# 5V_regulators.net
KiCad netlist of a schematic drawn in Altium Designer
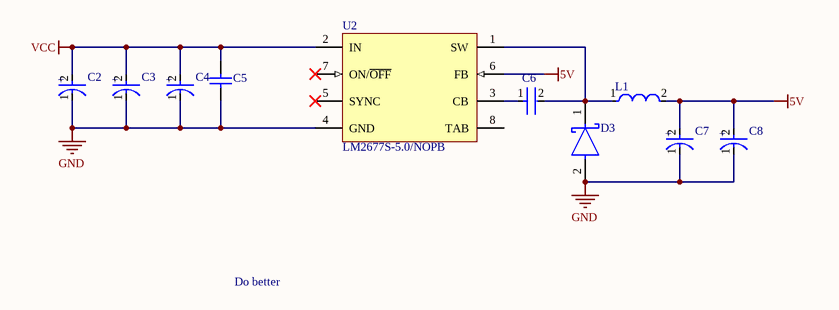
[diagram p0: 5V_regulators.SchDoc]

(export (version "E")
  (design (tool "Eeschema 10.0.6"))
  (components
    (comp (ref "C2")
      (value "16TQC15M")
      (footprint "FP-POSCAP-B2-MFG")
      (description "Molded Tantalum Polymer Capacitor 15uF 20% 16V life 2000Hours SMD 1411")
      (fields (field (name "VOLTAGE") "16V") (field (name "TOLERANCE") "20%"))
      (libsource (lib "Altium Content Vault") (part "cf48714ba7e38822c1575c7ec0b6d1f"))
    )
    (comp (ref "C3")
      (value "16TQC15M")
      (footprint "FP-POSCAP-B2-MFG")
      (description "Molded Tantalum Polymer Capacitor 15uF 20% 16V life 2000Hours SMD 1411")
      (fields (field (name "VOLTAGE") "16V") (field (name "TOLERANCE") "20%"))
      (libsource (lib "Altium Content Vault") (part "cf48714ba7e38822c1575c7ec0b6d1f"))
    )
    (comp (ref "C4")
      (value "16TQC15M")
      (footprint "FP-POSCAP-B2-MFG")
      (description "Molded Tantalum Polymer Capacitor 15uF 20% 16V life 2000Hours SMD 1411")
      (fields (field (name "VOLTAGE") "16V") (field (name "TOLERANCE") "20%"))
      (libsource (lib "Altium Content Vault") (part "cf48714ba7e38822c1575c7ec0b6d1f"))
    )
    (comp (ref "C5")
      (value "CAP 470nF 50V 1812(4532)")
      (footprint "CAPC1812(4532)125_M")
      (description "CAP 470nF 50V ±10% 1812 (4532 Metric) Thickness 1.25mm SMD")
      (fields (field (name "TOLERANCE") "Â±10%"))
      (libsource (lib "Altium Content Vault") (part "CAP"))
    )
    (comp (ref "C6")
      (value "C0805C103J5RACTU")
      (footprint "FP-C0805C-DN-MFG")
      (description "CAP CER 10000PF 50V X7R 0805")
      (fields
        (field (name "MANUFACTURER") "KEMET")
        (field (name "OCTOPART") "https://octopart.com/c0805c103j5ractu-kemet-133473")
      )
      (libsource (lib "Altium Content Vault") (part "b4654b650e69147ec39a6b967a45e02"))
    )
    (comp (ref "C7")
      (value "25SVPF180M")
      (footprint "FP-OS-CON-SMT-E12-MFG")
      (description "Conductive Polymer Aluminum Solid Capacitors (OS-CON) 180uF ±20% 25V")
      (fields (field (name "VOLTAGE") "25V") (field (name "TOLERANCE") "20%"))
      (libsource (lib "Altium Content Vault") (part "a00bbbee19879c290e62620ae7e47b1"))
    )
    (comp (ref "C8")
      (value "25SVPF180M")
      (footprint "FP-OS-CON-SMT-E12-MFG")
      (description "Conductive Polymer Aluminum Solid Capacitors (OS-CON) 180uF ±20% 25V")
      (fields (field (name "VOLTAGE") "25V") (field (name "TOLERANCE") "20%"))
      (libsource (lib "Altium Content Vault") (part "a00bbbee19879c290e62620ae7e47b1"))
    )
    (comp (ref "D3")
      (value "B540C-13-F")
      (footprint "FP-SMC-MFG")
      (description "DIODE SCHOTTKY 40V 5A SMC")
      (fields
        (field (name "OCTOPART") "https://octopart.com/b540c-13-f-diodes+inc.-325873")
        (field (name "MANUFACTURER") "Diodes Inc.")
      )
      (libsource (lib "Altium Content Vault") (part "1d6ec82d83fb6aee721767c19dac4b9"))
    )
    (comp (ref "L1")
      (value "SRP6060FA-220M")
      (footprint "FP-SRP6060FA-MFG")
      (description "IND,6.6X6.4X5.8MM,22UH,20%,5A,SH")
      (fields (field (name "TOLERANCE") "20%"))
      (libsource (lib "Altium Content Vault") (part "725321dda6339637d4d059423bc1c3c"))
    )
    (comp (ref "U2")
      (value "LM2677S-5.0/NOPB")
      (footprint "KTW0007B_N")
      (description "SIMPLE SWITCHER® High Efficiency 5A Step-Down Voltage Regulator with Sync, 7-pin TO-263, Pb-Free")
      (fields (field (name "MANUFACTURER") "Texas Instruments"))
      (libsource (lib "Altium Content Vault") (part "PM-REG-LM2670S-12"))
    )
  )
  (nets
    (net (code "1") (name "5V") (class "Default")
      (node (ref "C7") (pin "2") (pinfunction "A_2") (pintype "passive"))
      (node (ref "C8") (pin "2") (pinfunction "A_2") (pintype "passive"))
      (node (ref "L1") (pin "2") (pinfunction "2_2") (pintype "passive"))
      (node (ref "U2") (pin "6") (pinfunction "FB_6") (pintype "input"))
    )
    (net (code "2") (name "GND") (class "Default")
      (node (ref "C2") (pin "1") (pinfunction "C_1") (pintype "passive"))
      (node (ref "C3") (pin "1") (pinfunction "C_1") (pintype "passive"))
      (node (ref "C4") (pin "1") (pinfunction "C_1") (pintype "passive"))
      (node (ref "C5") (pin "1") (pinfunction "1_1") (pintype "passive"))
      (node (ref "C7") (pin "1") (pinfunction "C_1") (pintype "passive"))
      (node (ref "C8") (pin "1") (pinfunction "C_1") (pintype "passive"))
      (node (ref "D3") (pin "2") (pinfunction "A_2") (pintype "passive"))
      (node (ref "U2") (pin "4") (pinfunction "GND_4") (pintype "power_in"))
    )
    (net (code "3") (name "Net-(D3-C)") (class "Default")
      (node (ref "C6") (pin "2") (pinfunction "2_2") (pintype "passive"))
      (node (ref "D3") (pin "1") (pinfunction "C_1") (pintype "passive"))
      (node (ref "L1") (pin "1") (pinfunction "1_1") (pintype "passive"))
      (node (ref "U2") (pin "1") (pinfunction "SW_1") (pintype "power_in"))
    )
    (net (code "4") (name "Net-(U2-CB)") (class "Default")
      (node (ref "C6") (pin "1") (pinfunction "1_1") (pintype "passive"))
      (node (ref "U2") (pin "3") (pinfunction "CB_3") (pintype "passive"))
    )
    (net (code "5") (name "VCC") (class "Default")
      (node (ref "C2") (pin "2") (pinfunction "A_2") (pintype "passive"))
      (node (ref "C3") (pin "2") (pinfunction "A_2") (pintype "passive"))
      (node (ref "C4") (pin "2") (pinfunction "A_2") (pintype "passive"))
      (node (ref "C5") (pin "2") (pinfunction "2_2") (pintype "passive"))
      (node (ref "U2") (pin "2") (pinfunction "IN_2") (pintype "power_in"))
    )
    (net (code "6") (name "unconnected-(U2-ON{slash}~{OFF}-Pad7)") (class "Default")
      (node (ref "U2") (pin "7") (pinfunction "ON/~{OFF}_7") (pintype "input+no_connect"))
    )
    (net (code "7") (name "unconnected-(U2-SYNC-Pad5)") (class "Default")
      (node (ref "U2") (pin "5") (pinfunction "SYNC_5") (pintype "passive+no_connect"))
    )
    (net (code "8") (name "unconnected-(U2-TAB-Pad8)") (class "Default")
      (node (ref "U2") (pin "8") (pinfunction "TAB_8") (pintype "passive"))
    )
  )
)
